# 5V_Dual_Power_Supply.net
KiCad netlist of a schematic drawn in EAGLE
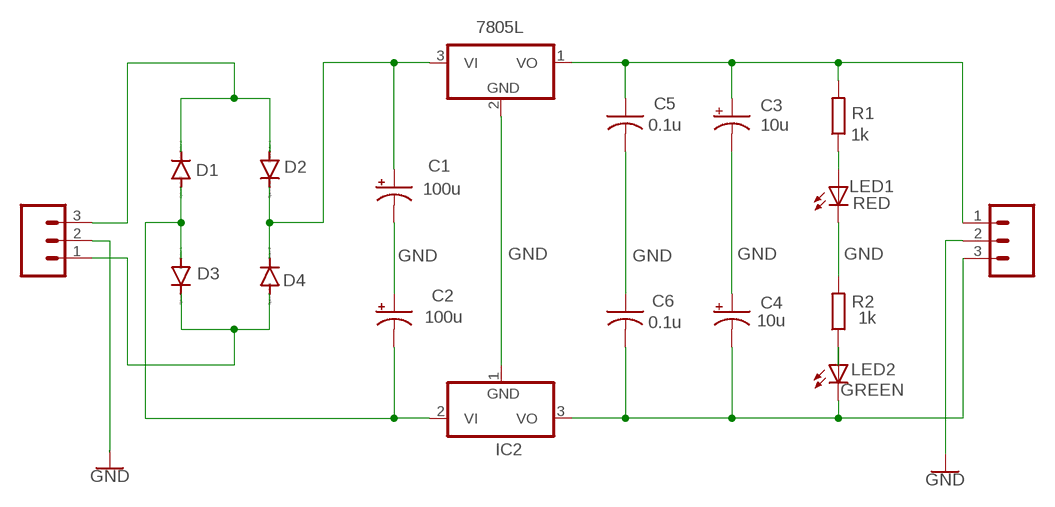
[diagram p0: schematic, sheet 1]

(export (version "E")
  (design (tool "Eeschema 10.0.6"))
  (components
    (comp (ref "C1")
      (value "100u")
      (footprint "eagle-import:E2-4")
      (libsource (lib "eagle-import") (part "CPOL-USE2-4"))
    )
    (comp (ref "C2")
      (value "100u")
      (footprint "eagle-import:E2-4")
      (libsource (lib "eagle-import") (part "CPOL-USE2-4"))
    )
    (comp (ref "C3")
      (value "10u")
      (footprint "eagle-import:E2-4")
      (libsource (lib "eagle-import") (part "CPOL-USE2-4"))
    )
    (comp (ref "C4")
      (value "10u")
      (footprint "eagle-import:E2-4")
      (libsource (lib "eagle-import") (part "CPOL-USE2-4"))
    )
    (comp (ref "C5")
      (value "0.1u")
      (footprint "eagle-import:C025-025X050")
      (libsource (lib "eagle-import") (part "C-US025-025X050"))
    )
    (comp (ref "C6")
      (value "0.1u")
      (footprint "eagle-import:C025-025X050")
      (libsource (lib "eagle-import") (part "C-US025-025X050"))
    )
    (comp (ref "D1")
      (value "1N4004")
      (footprint "eagle-import:DO41-10")
      (libsource (lib "eagle-import") (part "1N4004"))
    )
    (comp (ref "D2")
      (value "1N4004")
      (footprint "eagle-import:DO41-10")
      (libsource (lib "eagle-import") (part "1N4004"))
    )
    (comp (ref "D3")
      (value "1N4004")
      (footprint "eagle-import:DO41-10")
      (libsource (lib "eagle-import") (part "1N4004"))
    )
    (comp (ref "D4")
      (value "1N4004")
      (footprint "eagle-import:DO41-10")
      (libsource (lib "eagle-import") (part "1N4004"))
    )
    (comp (ref "IC1")
      (value "7805L")
      (footprint "eagle-import:TO92")
      (libsource (lib "eagle-import") (part "78L05"))
    )
    (comp (ref "IC2")
      (value "7905L")
      (footprint "eagle-import:TO92")
      (libsource (lib "eagle-import") (part "79L05"))
    )
    (comp (ref "J1")
      (value "CONN_03-SCREW-5MM")
      (footprint "eagle-import:SCREWTERMINAL-5MM-3")
      (libsource (lib "eagle-import") (part "CONN_03-SCREW-5MM"))
    )
    (comp (ref "J4")
      (value "CONN_03-SCREW-5MM")
      (footprint "eagle-import:SCREWTERMINAL-5MM-3")
      (libsource (lib "eagle-import") (part "CONN_03-SCREW-5MM"))
    )
    (comp (ref "LED1")
      (value "RED")
      (footprint "eagle-import:LED5MM")
      (libsource (lib "eagle-import") (part "LED5MM"))
    )
    (comp (ref "LED2")
      (value "GREEN")
      (footprint "eagle-import:LED5MM")
      (libsource (lib "eagle-import") (part "LED5MM"))
    )
    (comp (ref "R1")
      (value "1k")
      (footprint "eagle-import:0204_7")
      (libsource (lib "eagle-import") (part "R-EU_0204/7"))
    )
    (comp (ref "R2")
      (value "1k")
      (footprint "eagle-import:0204_7")
      (libsource (lib "eagle-import") (part "R-EU_0204/7"))
    )
  )
  (nets
    (net (code "1") (name "GND") (class "Default")
      (node (ref "C1") (pin "-") (pinfunction "-_-") (pintype "passive"))
      (node (ref "C2") (pin "+") (pinfunction "+_+") (pintype "passive"))
      (node (ref "C3") (pin "-") (pinfunction "-_-") (pintype "passive"))
      (node (ref "C4") (pin "+") (pinfunction "+_+") (pintype "passive"))
      (node (ref "C5") (pin "2") (pinfunction "2_2") (pintype "passive"))
      (node (ref "C6") (pin "1") (pinfunction "1_1") (pintype "passive"))
      (node (ref "IC1") (pin "2") (pinfunction "GND_2") (pintype "passive"))
      (node (ref "IC2") (pin "1") (pinfunction "GND_1") (pintype "passive"))
      (node (ref "J1") (pin "2") (pinfunction "2_2") (pintype "passive"))
      (node (ref "J4") (pin "2") (pinfunction "2_2") (pintype "passive"))
      (node (ref "LED1") (pin "K") (pinfunction "C_K") (pintype "passive"))
      (node (ref "R2") (pin "2") (pinfunction "2_2") (pintype "passive"))
    )
    (net (code "2") (name "Net-(D1-PadC)") (class "Default")
      (node (ref "D1") (pin "C") (pinfunction "C_C") (pintype "passive"))
      (node (ref "D2") (pin "A") (pinfunction "A_A") (pintype "passive"))
      (node (ref "J1") (pin "3") (pinfunction "3_3") (pintype "passive"))
    )
    (net (code "3") (name "Net-(D3-PadC)") (class "Default")
      (node (ref "D3") (pin "C") (pinfunction "C_C") (pintype "passive"))
      (node (ref "D4") (pin "A") (pinfunction "A_A") (pintype "passive"))
      (node (ref "J1") (pin "1") (pinfunction "1_1") (pintype "passive"))
    )
    (net (code "4") (name "Net-(IC1-VI)") (class "Default")
      (node (ref "C1") (pin "+") (pinfunction "+_+") (pintype "passive"))
      (node (ref "D2") (pin "C") (pinfunction "C_C") (pintype "passive"))
      (node (ref "D4") (pin "C") (pinfunction "C_C") (pintype "passive"))
      (node (ref "IC1") (pin "3") (pinfunction "VI_3") (pintype "input"))
    )
    (net (code "5") (name "Net-(IC1-VO)") (class "Default")
      (node (ref "C3") (pin "+") (pinfunction "+_+") (pintype "passive"))
      (node (ref "C5") (pin "1") (pinfunction "1_1") (pintype "passive"))
      (node (ref "IC1") (pin "1") (pinfunction "VO_1") (pintype "passive"))
      (node (ref "J4") (pin "1") (pinfunction "1_1") (pintype "passive"))
      (node (ref "R1") (pin "2") (pinfunction "2_2") (pintype "passive"))
    )
    (net (code "6") (name "Net-(IC2-VI)") (class "Default")
      (node (ref "C2") (pin "-") (pinfunction "-_-") (pintype "passive"))
      (node (ref "D1") (pin "A") (pinfunction "A_A") (pintype "passive"))
      (node (ref "D3") (pin "A") (pinfunction "A_A") (pintype "passive"))
      (node (ref "IC2") (pin "2") (pinfunction "VI_2") (pintype "input"))
    )
    (net (code "7") (name "Net-(IC2-VO)") (class "Default")
      (node (ref "C4") (pin "-") (pinfunction "-_-") (pintype "passive"))
      (node (ref "C6") (pin "2") (pinfunction "2_2") (pintype "passive"))
      (node (ref "IC2") (pin "3") (pinfunction "VO_3") (pintype "passive"))
      (node (ref "J4") (pin "3") (pinfunction "3_3") (pintype "passive"))
      (node (ref "LED2") (pin "K") (pinfunction "C_K") (pintype "passive"))
    )
    (net (code "8") (name "Net-(LED1-PadA)") (class "Default")
      (node (ref "LED1") (pin "A") (pinfunction "A_A") (pintype "passive"))
      (node (ref "R1") (pin "1") (pinfunction "1_1") (pintype "passive"))
    )
    (net (code "9") (name "Net-(LED2-PadA)") (class "Default")
      (node (ref "LED2") (pin "A") (pinfunction "A_A") (pintype "passive"))
      (node (ref "R2") (pin "1") (pinfunction "1_1") (pintype "passive"))
    )
  )
)
